# t-maze-shield.net
KiCad netlist of a schematic drawn in EAGLE
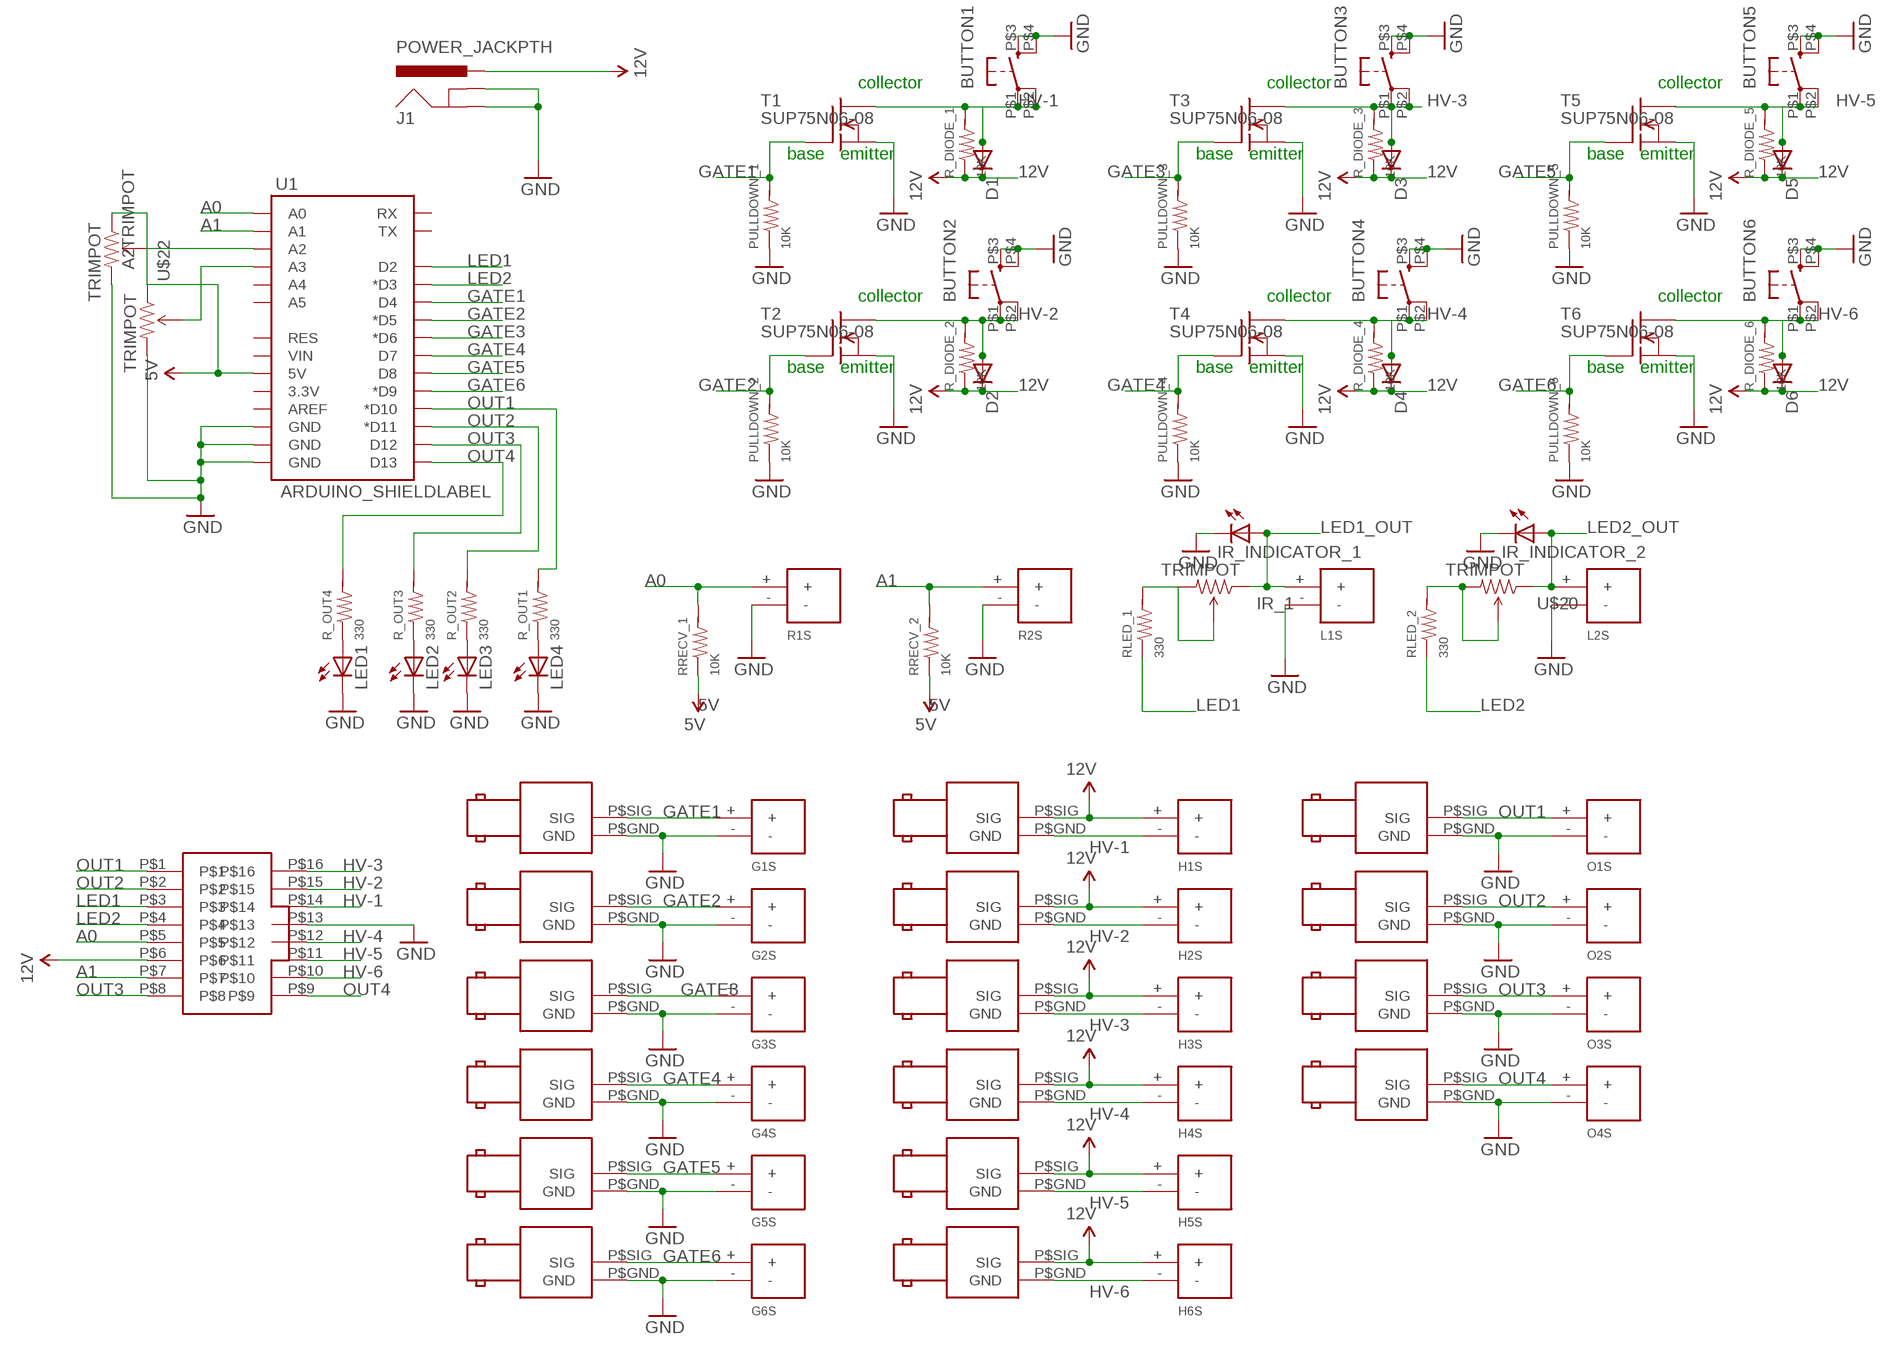
[diagram p0: schematic, sheet 1]

(export (version "E")
  (design (tool "Eeschema 10.0.6"))
  (components
    (comp (ref "A2TRIMPOT")
      (value "TRIMPOT")
      (footprint "eagle-import:3362U-2")
      (libsource (lib "eagle-import") (part "TRIMPOT"))
    )
    (comp (ref "BUTTON1")
      (value "TAC_SWITCHKSA_SEALED")
      (footprint "eagle-import:KSA_SEALED_TAC_SWITCH")
      (libsource (lib "eagle-import") (part "TAC_SWITCHKSA_SEALED"))
    )
    (comp (ref "BUTTON2")
      (value "TAC_SWITCHKSA_SEALED")
      (footprint "eagle-import:KSA_SEALED_TAC_SWITCH")
      (libsource (lib "eagle-import") (part "TAC_SWITCHKSA_SEALED"))
    )
    (comp (ref "BUTTON3")
      (value "TAC_SWITCHKSA_SEALED")
      (footprint "eagle-import:KSA_SEALED_TAC_SWITCH")
      (libsource (lib "eagle-import") (part "TAC_SWITCHKSA_SEALED"))
    )
    (comp (ref "BUTTON4")
      (value "TAC_SWITCHKSA_SEALED")
      (footprint "eagle-import:KSA_SEALED_TAC_SWITCH")
      (libsource (lib "eagle-import") (part "TAC_SWITCHKSA_SEALED"))
    )
    (comp (ref "BUTTON5")
      (value "TAC_SWITCHKSA_SEALED")
      (footprint "eagle-import:KSA_SEALED_TAC_SWITCH")
      (libsource (lib "eagle-import") (part "TAC_SWITCHKSA_SEALED"))
    )
    (comp (ref "BUTTON6")
      (value "TAC_SWITCHKSA_SEALED")
      (footprint "eagle-import:KSA_SEALED_TAC_SWITCH")
      (libsource (lib "eagle-import") (part "TAC_SWITCHKSA_SEALED"))
    )
    (comp (ref "D1")
      (value "DIODE1N4148")
      (footprint "eagle-import:DIODE-1N4148")
      (libsource (lib "eagle-import") (part "DIODE1N4148"))
    )
    (comp (ref "D2")
      (value "DIODE1N4148")
      (footprint "eagle-import:DIODE-1N4148")
      (libsource (lib "eagle-import") (part "DIODE1N4148"))
    )
    (comp (ref "D3")
      (value "DIODE1N4148")
      (footprint "eagle-import:DIODE-1N4148")
      (libsource (lib "eagle-import") (part "DIODE1N4148"))
    )
    (comp (ref "D4")
      (value "DIODE1N4148")
      (footprint "eagle-import:DIODE-1N4148")
      (libsource (lib "eagle-import") (part "DIODE1N4148"))
    )
    (comp (ref "D5")
      (value "DIODE1N4148")
      (footprint "eagle-import:DIODE-1N4148")
      (libsource (lib "eagle-import") (part "DIODE1N4148"))
    )
    (comp (ref "D6")
      (value "DIODE1N4148")
      (footprint "eagle-import:DIODE-1N4148")
      (libsource (lib "eagle-import") (part "DIODE1N4148"))
    )
    (comp (ref "G1S")
      (value "SCREW_TERM_2")
      (footprint "eagle-import:SCREW_TERM")
      (libsource (lib "eagle-import") (part "SCREW_TERM_2"))
    )
    (comp (ref "G2S")
      (value "SCREW_TERM_2")
      (footprint "eagle-import:SCREW_TERM")
      (libsource (lib "eagle-import") (part "SCREW_TERM_2"))
    )
    (comp (ref "G3S")
      (value "SCREW_TERM_2")
      (footprint "eagle-import:SCREW_TERM")
      (libsource (lib "eagle-import") (part "SCREW_TERM_2"))
    )
    (comp (ref "G4S")
      (value "SCREW_TERM_2")
      (footprint "eagle-import:SCREW_TERM")
      (libsource (lib "eagle-import") (part "SCREW_TERM_2"))
    )
    (comp (ref "G5S")
      (value "SCREW_TERM_2")
      (footprint "eagle-import:SCREW_TERM")
      (libsource (lib "eagle-import") (part "SCREW_TERM_2"))
    )
    (comp (ref "G6S")
      (value "SCREW_TERM_2")
      (footprint "eagle-import:SCREW_TERM")
      (libsource (lib "eagle-import") (part "SCREW_TERM_2"))
    )
    (comp (ref "GATE1")
      (value "BNC_RIGHT_ANGLE")
      (footprint "eagle-import:BNC_RIGHT_ANGLE")
      (libsource (lib "eagle-import") (part "BNC_RIGHT_ANGLE"))
    )
    (comp (ref "GATE2")
      (value "BNC_RIGHT_ANGLE")
      (footprint "eagle-import:BNC_RIGHT_ANGLE")
      (libsource (lib "eagle-import") (part "BNC_RIGHT_ANGLE"))
    )
    (comp (ref "GATE3")
      (value "BNC_RIGHT_ANGLE")
      (footprint "eagle-import:BNC_RIGHT_ANGLE")
      (libsource (lib "eagle-import") (part "BNC_RIGHT_ANGLE"))
    )
    (comp (ref "GATE4")
      (value "BNC_RIGHT_ANGLE")
      (footprint "eagle-import:BNC_RIGHT_ANGLE")
      (libsource (lib "eagle-import") (part "BNC_RIGHT_ANGLE"))
    )
    (comp (ref "GATE5")
      (value "BNC_RIGHT_ANGLE")
      (footprint "eagle-import:BNC_RIGHT_ANGLE")
      (libsource (lib "eagle-import") (part "BNC_RIGHT_ANGLE"))
    )
    (comp (ref "GATE6")
      (value "BNC_RIGHT_ANGLE")
      (footprint "eagle-import:BNC_RIGHT_ANGLE")
      (libsource (lib "eagle-import") (part "BNC_RIGHT_ANGLE"))
    )
    (comp (ref "H1S")
      (value "SCREW_TERM_2")
      (footprint "eagle-import:SCREW_TERM")
      (libsource (lib "eagle-import") (part "SCREW_TERM_2"))
    )
    (comp (ref "H2S")
      (value "SCREW_TERM_2")
      (footprint "eagle-import:SCREW_TERM")
      (libsource (lib "eagle-import") (part "SCREW_TERM_2"))
    )
    (comp (ref "H3S")
      (value "SCREW_TERM_2")
      (footprint "eagle-import:SCREW_TERM")
      (libsource (lib "eagle-import") (part "SCREW_TERM_2"))
    )
    (comp (ref "H4S")
      (value "SCREW_TERM_2")
      (footprint "eagle-import:SCREW_TERM")
      (libsource (lib "eagle-import") (part "SCREW_TERM_2"))
    )
    (comp (ref "H5S")
      (value "SCREW_TERM_2")
      (footprint "eagle-import:SCREW_TERM")
      (libsource (lib "eagle-import") (part "SCREW_TERM_2"))
    )
    (comp (ref "H6S")
      (value "SCREW_TERM_2")
      (footprint "eagle-import:SCREW_TERM")
      (libsource (lib "eagle-import") (part "SCREW_TERM_2"))
    )
    (comp (ref "I/O1")
      (value "BNC_RIGHT_ANGLE")
      (footprint "eagle-import:BNC_RIGHT_ANGLE")
      (libsource (lib "eagle-import") (part "BNC_RIGHT_ANGLE"))
    )
    (comp (ref "I/O2")
      (value "BNC_RIGHT_ANGLE")
      (footprint "eagle-import:BNC_RIGHT_ANGLE")
      (libsource (lib "eagle-import") (part "BNC_RIGHT_ANGLE"))
    )
    (comp (ref "I/O3")
      (value "BNC_RIGHT_ANGLE")
      (footprint "eagle-import:BNC_RIGHT_ANGLE")
      (libsource (lib "eagle-import") (part "BNC_RIGHT_ANGLE"))
    )
    (comp (ref "I/O4")
      (value "BNC_RIGHT_ANGLE")
      (footprint "eagle-import:BNC_RIGHT_ANGLE")
      (libsource (lib "eagle-import") (part "BNC_RIGHT_ANGLE"))
    )
    (comp (ref "IDC-16")
      (value "IDC_16PIN")
      (footprint "eagle-import:IDC_16PIN")
      (libsource (lib "eagle-import") (part "IDC_16PIN"))
    )
    (comp (ref "IR_1")
      (value "TRIMPOT")
      (footprint "eagle-import:3362U-2")
      (libsource (lib "eagle-import") (part "TRIMPOT"))
    )
    (comp (ref "IR_INDICATOR_1")
      (value "LED5MM")
      (footprint "eagle-import:LED5MM")
      (libsource (lib "eagle-import") (part "LED5MM"))
    )
    (comp (ref "IR_INDICATOR_2")
      (value "LED5MM")
      (footprint "eagle-import:LED5MM")
      (libsource (lib "eagle-import") (part "LED5MM"))
    )
    (comp (ref "J1")
      (value "POWER_JACKPTH")
      (footprint "eagle-import:POWER_JACK_PTH")
      (libsource (lib "eagle-import") (part "POWER_JACKPTH"))
    )
    (comp (ref "L1S")
      (value "SCREW_TERM_2")
      (footprint "eagle-import:SCREW_TERM")
      (libsource (lib "eagle-import") (part "SCREW_TERM_2"))
    )
    (comp (ref "L2S")
      (value "SCREW_TERM_2")
      (footprint "eagle-import:SCREW_TERM")
      (libsource (lib "eagle-import") (part "SCREW_TERM_2"))
    )
    (comp (ref "LED1")
      (value "LED5MM")
      (footprint "eagle-import:LED5MM")
      (libsource (lib "eagle-import") (part "LED5MM"))
    )
    (comp (ref "LED2")
      (value "LED5MM")
      (footprint "eagle-import:LED5MM")
      (libsource (lib "eagle-import") (part "LED5MM"))
    )
    (comp (ref "LED3")
      (value "LED5MM")
      (footprint "eagle-import:LED5MM")
      (libsource (lib "eagle-import") (part "LED5MM"))
    )
    (comp (ref "LED4")
      (value "LED5MM")
      (footprint "eagle-import:LED5MM")
      (libsource (lib "eagle-import") (part "LED5MM"))
    )
    (comp (ref "O1S")
      (value "SCREW_TERM_2")
      (footprint "eagle-import:SCREW_TERM")
      (libsource (lib "eagle-import") (part "SCREW_TERM_2"))
    )
    (comp (ref "O2S")
      (value "SCREW_TERM_2")
      (footprint "eagle-import:SCREW_TERM")
      (libsource (lib "eagle-import") (part "SCREW_TERM_2"))
    )
    (comp (ref "O3S")
      (value "SCREW_TERM_2")
      (footprint "eagle-import:SCREW_TERM")
      (libsource (lib "eagle-import") (part "SCREW_TERM_2"))
    )
    (comp (ref "O4S")
      (value "SCREW_TERM_2")
      (footprint "eagle-import:SCREW_TERM")
      (libsource (lib "eagle-import") (part "SCREW_TERM_2"))
    )
    (comp (ref "OUT1")
      (value "BNC_RIGHT_ANGLE")
      (footprint "eagle-import:BNC_RIGHT_ANGLE")
      (libsource (lib "eagle-import") (part "BNC_RIGHT_ANGLE"))
    )
    (comp (ref "OUT2")
      (value "BNC_RIGHT_ANGLE")
      (footprint "eagle-import:BNC_RIGHT_ANGLE")
      (libsource (lib "eagle-import") (part "BNC_RIGHT_ANGLE"))
    )
    (comp (ref "OUT3")
      (value "BNC_RIGHT_ANGLE")
      (footprint "eagle-import:BNC_RIGHT_ANGLE")
      (libsource (lib "eagle-import") (part "BNC_RIGHT_ANGLE"))
    )
    (comp (ref "OUT4")
      (value "BNC_RIGHT_ANGLE")
      (footprint "eagle-import:BNC_RIGHT_ANGLE")
      (libsource (lib "eagle-import") (part "BNC_RIGHT_ANGLE"))
    )
    (comp (ref "OUT5")
      (value "BNC_RIGHT_ANGLE")
      (footprint "eagle-import:BNC_RIGHT_ANGLE")
      (libsource (lib "eagle-import") (part "BNC_RIGHT_ANGLE"))
    )
    (comp (ref "OUT6")
      (value "BNC_RIGHT_ANGLE")
      (footprint "eagle-import:BNC_RIGHT_ANGLE")
      (libsource (lib "eagle-import") (part "BNC_RIGHT_ANGLE"))
    )
    (comp (ref "PULLDOWN_1")
      (value "10K")
      (footprint "eagle-import:RESISTOR_PTH")
      (libsource (lib "eagle-import") (part "RESISTOR_PTH"))
    )
    (comp (ref "PULLDOWN_2")
      (value "10K")
      (footprint "eagle-import:RESISTOR_PTH")
      (libsource (lib "eagle-import") (part "RESISTOR_PTH"))
    )
    (comp (ref "PULLDOWN_3")
      (value "10K")
      (footprint "eagle-import:RESISTOR_PTH")
      (libsource (lib "eagle-import") (part "RESISTOR_PTH"))
    )
    (comp (ref "PULLDOWN_4")
      (value "10K")
      (footprint "eagle-import:RESISTOR_PTH")
      (libsource (lib "eagle-import") (part "RESISTOR_PTH"))
    )
    (comp (ref "PULLDOWN_5")
      (value "10K")
      (footprint "eagle-import:RESISTOR_PTH")
      (libsource (lib "eagle-import") (part "RESISTOR_PTH"))
    )
    (comp (ref "PULLDOWN_6")
      (value "10K")
      (footprint "eagle-import:RESISTOR_PTH")
      (libsource (lib "eagle-import") (part "RESISTOR_PTH"))
    )
    (comp (ref "R1S")
      (value "SCREW_TERM_2")
      (footprint "eagle-import:SCREW_TERM")
      (libsource (lib "eagle-import") (part "SCREW_TERM_2"))
    )
    (comp (ref "R2S")
      (value "SCREW_TERM_2")
      (footprint "eagle-import:SCREW_TERM")
      (libsource (lib "eagle-import") (part "SCREW_TERM_2"))
    )
    (comp (ref "RLED_1")
      (value "330")
      (footprint "eagle-import:RESISTOR_PTH")
      (libsource (lib "eagle-import") (part "RESISTOR_PTH"))
    )
    (comp (ref "RLED_2")
      (value "330")
      (footprint "eagle-import:RESISTOR_PTH")
      (libsource (lib "eagle-import") (part "RESISTOR_PTH"))
    )
    (comp (ref "RRECV_1")
      (value "10K")
      (footprint "eagle-import:RESISTOR_PTH")
      (libsource (lib "eagle-import") (part "RESISTOR_PTH"))
    )
    (comp (ref "RRECV_2")
      (value "10K")
      (footprint "eagle-import:RESISTOR_PTH")
      (libsource (lib "eagle-import") (part "RESISTOR_PTH"))
    )
    (comp (ref "R_DIODE_1")
      (value "10K")
      (footprint "eagle-import:RESISTOR_PTH")
      (libsource (lib "eagle-import") (part "RESISTOR_PTH"))
    )
    (comp (ref "R_DIODE_2")
      (value "10K")
      (footprint "eagle-import:RESISTOR_PTH")
      (libsource (lib "eagle-import") (part "RESISTOR_PTH"))
    )
    (comp (ref "R_DIODE_3")
      (value "10K")
      (footprint "eagle-import:RESISTOR_PTH")
      (libsource (lib "eagle-import") (part "RESISTOR_PTH"))
    )
    (comp (ref "R_DIODE_4")
      (value "10K")
      (footprint "eagle-import:RESISTOR_PTH")
      (libsource (lib "eagle-import") (part "RESISTOR_PTH"))
    )
    (comp (ref "R_DIODE_5")
      (value "10K")
      (footprint "eagle-import:RESISTOR_PTH")
      (libsource (lib "eagle-import") (part "RESISTOR_PTH"))
    )
    (comp (ref "R_DIODE_6")
      (value "10K")
      (footprint "eagle-import:RESISTOR_PTH")
      (libsource (lib "eagle-import") (part "RESISTOR_PTH"))
    )
    (comp (ref "R_OUT1")
      (value "330")
      (footprint "eagle-import:RESISTOR_PTH")
      (libsource (lib "eagle-import") (part "RESISTOR_PTH"))
    )
    (comp (ref "R_OUT2")
      (value "330")
      (footprint "eagle-import:RESISTOR_PTH")
      (libsource (lib "eagle-import") (part "RESISTOR_PTH"))
    )
    (comp (ref "R_OUT3")
      (value "330")
      (footprint "eagle-import:RESISTOR_PTH")
      (libsource (lib "eagle-import") (part "RESISTOR_PTH"))
    )
    (comp (ref "R_OUT4")
      (value "330")
      (footprint "eagle-import:RESISTOR_PTH")
      (libsource (lib "eagle-import") (part "RESISTOR_PTH"))
    )
    (comp (ref "T1")
      (value "SUP75N06-08")
      (footprint "eagle-import:TO220")
      (libsource (lib "eagle-import") (part "SUP75N06-08"))
    )
    (comp (ref "T2")
      (value "SUP75N06-08")
      (footprint "eagle-import:TO220")
      (libsource (lib "eagle-import") (part "SUP75N06-08"))
    )
    (comp (ref "T3")
      (value "SUP75N06-08")
      (footprint "eagle-import:TO220")
      (libsource (lib "eagle-import") (part "SUP75N06-08"))
    )
    (comp (ref "T4")
      (value "SUP75N06-08")
      (footprint "eagle-import:TO220")
      (libsource (lib "eagle-import") (part "SUP75N06-08"))
    )
    (comp (ref "T5")
      (value "SUP75N06-08")
      (footprint "eagle-import:TO220")
      (libsource (lib "eagle-import") (part "SUP75N06-08"))
    )
    (comp (ref "T6")
      (value "SUP75N06-08")
      (footprint "eagle-import:TO220")
      (libsource (lib "eagle-import") (part "SUP75N06-08"))
    )
    (comp (ref "U$20")
      (value "TRIMPOT")
      (footprint "eagle-import:3362U-2")
      (libsource (lib "eagle-import") (part "TRIMPOT"))
    )
    (comp (ref "U$22")
      (value "TRIMPOT")
      (footprint "eagle-import:3362U-2")
      (libsource (lib "eagle-import") (part "TRIMPOT"))
    )
    (comp (ref "U1")
      (value "ARDUINO_SHIELDLABEL")
      (footprint "eagle-import:DUEMILANOVE_SHIELD")
      (libsource (lib "eagle-import") (part "ARDUINO_SHIELDLABEL"))
    )
  )
  (nets
    (net (code "1") (name "/A0") (class "Default")
      (node (ref "IDC-16") (pin "P$5") (pinfunction "P$5_P$5") (pintype "bidirectional"))
      (node (ref "R1S") (pin "+") (pinfunction "+_+") (pintype "bidirectional"))
      (node (ref "RRECV_1") (pin "P$2") (pinfunction "P$2_P$2") (pintype "bidirectional"))
      (node (ref "U1") (pin "A0") (pinfunction "A0_A0") (pintype "bidirectional"))
    )
    (net (code "2") (name "/A1") (class "Default")
      (node (ref "IDC-16") (pin "P$7") (pinfunction "P$7_P$7") (pintype "bidirectional"))
      (node (ref "R2S") (pin "+") (pinfunction "+_+") (pintype "bidirectional"))
      (node (ref "RRECV_2") (pin "P$2") (pinfunction "P$2_P$2") (pintype "bidirectional"))
      (node (ref "U1") (pin "A1") (pinfunction "A1_A1") (pintype "bidirectional"))
    )
    (net (code "3") (name "/GATE1") (class "Default")
      (node (ref "G1S") (pin "+") (pinfunction "+_+") (pintype "bidirectional"))
      (node (ref "GATE1") (pin "P$SIG") (pinfunction "SIG_P$SIG") (pintype "bidirectional"))
      (node (ref "PULLDOWN_1") (pin "P$2") (pinfunction "P$2_P$2") (pintype "bidirectional"))
      (node (ref "T1") (pin "1") (pinfunction "G_1") (pintype "passive"))
      (node (ref "U1") (pin "D4") (pinfunction "D4_D4") (pintype "bidirectional"))
    )
    (net (code "4") (name "/GATE2") (class "Default")
      (node (ref "G2S") (pin "+") (pinfunction "+_+") (pintype "bidirectional"))
      (node (ref "GATE2") (pin "P$SIG") (pinfunction "SIG_P$SIG") (pintype "bidirectional"))
      (node (ref "PULLDOWN_2") (pin "P$2") (pinfunction "P$2_P$2") (pintype "bidirectional"))
      (node (ref "T2") (pin "1") (pinfunction "G_1") (pintype "passive"))
      (node (ref "U1") (pin "D5") (pinfunction "*D5_D5") (pintype "bidirectional"))
    )
    (net (code "5") (name "/GATE3") (class "Default")
      (node (ref "G3S") (pin "+") (pinfunction "+_+") (pintype "bidirectional"))
      (node (ref "GATE3") (pin "P$SIG") (pinfunction "SIG_P$SIG") (pintype "bidirectional"))
      (node (ref "PULLDOWN_3") (pin "P$2") (pinfunction "P$2_P$2") (pintype "bidirectional"))
      (node (ref "T3") (pin "1") (pinfunction "G_1") (pintype "passive"))
      (node (ref "U1") (pin "D6") (pinfunction "*D6_D6") (pintype "bidirectional"))
    )
    (net (code "6") (name "/GATE4") (class "Default")
      (node (ref "G4S") (pin "+") (pinfunction "+_+") (pintype "bidirectional"))
      (node (ref "GATE4") (pin "P$SIG") (pinfunction "SIG_P$SIG") (pintype "bidirectional"))
      (node (ref "PULLDOWN_4") (pin "P$2") (pinfunction "P$2_P$2") (pintype "bidirectional"))
      (node (ref "T4") (pin "1") (pinfunction "G_1") (pintype "passive"))
      (node (ref "U1") (pin "D7") (pinfunction "D7_D7") (pintype "bidirectional"))
    )
    (net (code "7") (name "/GATE5") (class "Default")
      (node (ref "G5S") (pin "+") (pinfunction "+_+") (pintype "bidirectional"))
      (node (ref "GATE5") (pin "P$SIG") (pinfunction "SIG_P$SIG") (pintype "bidirectional"))
      (node (ref "PULLDOWN_5") (pin "P$2") (pinfunction "P$2_P$2") (pintype "bidirectional"))
      (node (ref "T5") (pin "1") (pinfunction "G_1") (pintype "passive"))
      (node (ref "U1") (pin "D8") (pinfunction "D8_D8") (pintype "bidirectional"))
    )
    (net (code "8") (name "/GATE6") (class "Default")
      (node (ref "G6S") (pin "+") (pinfunction "+_+") (pintype "bidirectional"))
      (node (ref "GATE6") (pin "P$SIG") (pinfunction "SIG_P$SIG") (pintype "bidirectional"))
      (node (ref "PULLDOWN_6") (pin "P$2") (pinfunction "P$2_P$2") (pintype "bidirectional"))
      (node (ref "T6") (pin "1") (pinfunction "G_1") (pintype "passive"))
      (node (ref "U1") (pin "D9") (pinfunction "*D9_D9") (pintype "bidirectional"))
    )
    (net (code "9") (name "/HV-1") (class "Default")
      (node (ref "BUTTON1") (pin "P$1") (pinfunction "1_P$1") (pintype "passive"))
      (node (ref "BUTTON1") (pin "P$2") (pinfunction "2_P$2") (pintype "passive"))
      (node (ref "D1") (pin "A") (pinfunction "A_A") (pintype "passive"))
      (node (ref "H1S") (pin "-") (pinfunction "-_-") (pintype "bidirectional"))
      (node (ref "IDC-16") (pin "P$14") (pinfunction "P$14_P$14") (pintype "bidirectional"))
      (node (ref "OUT1") (pin "P$GND") (pinfunction "GND_P$GND") (pintype "bidirectional"))
      (node (ref "R_DIODE_1") (pin "P$2") (pinfunction "P$2_P$2") (pintype "bidirectional"))
      (node (ref "T1") (pin "2") (pinfunction "D_2") (pintype "passive"))
    )
    (net (code "10") (name "/HV-2") (class "Default")
      (node (ref "BUTTON2") (pin "P$1") (pinfunction "1_P$1") (pintype "passive"))
      (node (ref "BUTTON2") (pin "P$2") (pinfunction "2_P$2") (pintype "passive"))
      (node (ref "D2") (pin "A") (pinfunction "A_A") (pintype "passive"))
      (node (ref "H2S") (pin "-") (pinfunction "-_-") (pintype "bidirectional"))
      (node (ref "IDC-16") (pin "P$15") (pinfunction "P$15_P$15") (pintype "bidirectional"))
      (node (ref "OUT2") (pin "P$GND") (pinfunction "GND_P$GND") (pintype "bidirectional"))
      (node (ref "R_DIODE_2") (pin "P$2") (pinfunction "P$2_P$2") (pintype "bidirectional"))
      (node (ref "T2") (pin "2") (pinfunction "D_2") (pintype "passive"))
    )
    (net (code "11") (name "/HV-3") (class "Default")
      (node (ref "BUTTON3") (pin "P$1") (pinfunction "1_P$1") (pintype "passive"))
      (node (ref "BUTTON3") (pin "P$2") (pinfunction "2_P$2") (pintype "passive"))
      (node (ref "D3") (pin "A") (pinfunction "A_A") (pintype "passive"))
      (node (ref "H3S") (pin "-") (pinfunction "-_-") (pintype "bidirectional"))
      (node (ref "IDC-16") (pin "P$16") (pinfunction "P$16_P$16") (pintype "bidirectional"))
      (node (ref "OUT3") (pin "P$GND") (pinfunction "GND_P$GND") (pintype "bidirectional"))
      (node (ref "R_DIODE_3") (pin "P$2") (pinfunction "P$2_P$2") (pintype "bidirectional"))
      (node (ref "T3") (pin "2") (pinfunction "D_2") (pintype "passive"))
    )
    (net (code "12") (name "/HV-4") (class "Default")
      (node (ref "BUTTON4") (pin "P$1") (pinfunction "1_P$1") (pintype "passive"))
      (node (ref "BUTTON4") (pin "P$2") (pinfunction "2_P$2") (pintype "passive"))
      (node (ref "D4") (pin "A") (pinfunction "A_A") (pintype "passive"))
      (node (ref "H4S") (pin "-") (pinfunction "-_-") (pintype "bidirectional"))
      (node (ref "IDC-16") (pin "P$12") (pinfunction "P$12_P$12") (pintype "bidirectional"))
      (node (ref "OUT4") (pin "P$GND") (pinfunction "GND_P$GND") (pintype "bidirectional"))
      (node (ref "R_DIODE_4") (pin "P$2") (pinfunction "P$2_P$2") (pintype "bidirectional"))
      (node (ref "T4") (pin "2") (pinfunction "D_2") (pintype "passive"))
    )
    (net (code "13") (name "/HV-5") (class "Default")
      (node (ref "BUTTON5") (pin "P$1") (pinfunction "1_P$1") (pintype "passive"))
      (node (ref "BUTTON5") (pin "P$2") (pinfunction "2_P$2") (pintype "passive"))
      (node (ref "D5") (pin "A") (pinfunction "A_A") (pintype "passive"))
      (node (ref "H5S") (pin "-") (pinfunction "-_-") (pintype "bidirectional"))
      (node (ref "IDC-16") (pin "P$11") (pinfunction "P$11_P$11") (pintype "bidirectional"))
      (node (ref "OUT5") (pin "P$GND") (pinfunction "GND_P$GND") (pintype "bidirectional"))
      (node (ref "R_DIODE_5") (pin "P$2") (pinfunction "P$2_P$2") (pintype "bidirectional"))
      (node (ref "T5") (pin "2") (pinfunction "D_2") (pintype "passive"))
    )
    (net (code "14") (name "/HV-6") (class "Default")
      (node (ref "BUTTON6") (pin "P$1") (pinfunction "1_P$1") (pintype "passive"))
      (node (ref "BUTTON6") (pin "P$2") (pinfunction "2_P$2") (pintype "passive"))
      (node (ref "D6") (pin "A") (pinfunction "A_A") (pintype "passive"))
      (node (ref "H6S") (pin "-") (pinfunction "-_-") (pintype "bidirectional"))
      (node (ref "IDC-16") (pin "P$10") (pinfunction "P$10_P$10") (pintype "bidirectional"))
      (node (ref "OUT6") (pin "P$GND") (pinfunction "GND_P$GND") (pintype "bidirectional"))
      (node (ref "R_DIODE_6") (pin "P$2") (pinfunction "P$2_P$2") (pintype "bidirectional"))
      (node (ref "T6") (pin "2") (pinfunction "D_2") (pintype "passive"))
    )
    (net (code "15") (name "/LED1") (class "Default")
      (node (ref "IDC-16") (pin "P$3") (pinfunction "P$3_P$3") (pintype "bidirectional"))
      (node (ref "RLED_1") (pin "P$1") (pinfunction "P$1_P$1") (pintype "bidirectional"))
      (node (ref "U1") (pin "D2") (pinfunction "D2_D2") (pintype "bidirectional"))
    )
    (net (code "16") (name "/LED1_OUT") (class "Default")
      (node (ref "IR_1") (pin "1") (pinfunction "CCW_1") (pintype "passive"))
      (node (ref "IR_INDICATOR_1") (pin "A") (pinfunction "A_A") (pintype "passive"))
      (node (ref "L1S") (pin "+") (pinfunction "+_+") (pintype "bidirectional"))
    )
    (net (code "17") (name "/LED2") (class "Default")
      (node (ref "IDC-16") (pin "P$4") (pinfunction "P$4_P$4") (pintype "bidirectional"))
      (node (ref "RLED_2") (pin "P$1") (pinfunction "P$1_P$1") (pintype "bidirectional"))
      (node (ref "U1") (pin "D3") (pinfunction "*D3_D3") (pintype "bidirectional"))
    )
    (net (code "18") (name "/LED2_OUT") (class "Default")
      (node (ref "IR_INDICATOR_2") (pin "A") (pinfunction "A_A") (pintype "passive"))
      (node (ref "L2S") (pin "+") (pinfunction "+_+") (pintype "bidirectional"))
      (node (ref "U$20") (pin "1") (pinfunction "CCW_1") (pintype "passive"))
    )
    (net (code "19") (name "/OUT1") (class "Default")
      (node (ref "I/O1") (pin "P$SIG") (pinfunction "SIG_P$SIG") (pintype "bidirectional"))
      (node (ref "IDC-16") (pin "P$1") (pinfunction "P$1_P$1") (pintype "bidirectional"))
      (node (ref "O1S") (pin "+") (pinfunction "+_+") (pintype "bidirectional"))
      (node (ref "R_OUT1") (pin "P$2") (pinfunction "P$2_P$2") (pintype "bidirectional"))
      (node (ref "U1") (pin "D10") (pinfunction "*D10_D10") (pintype "bidirectional"))
    )
    (net (code "20") (name "/OUT2") (class "Default")
      (node (ref "I/O2") (pin "P$SIG") (pinfunction "SIG_P$SIG") (pintype "bidirectional"))
      (node (ref "IDC-16") (pin "P$2") (pinfunction "P$2_P$2") (pintype "bidirectional"))
      (node (ref "O2S") (pin "+") (pinfunction "+_+") (pintype "bidirectional"))
      (node (ref "R_OUT2") (pin "P$2") (pinfunction "P$2_P$2") (pintype "bidirectional"))
      (node (ref "U1") (pin "D11") (pinfunction "*D11_D11") (pintype "bidirectional"))
    )
    (net (code "21") (name "/OUT3") (class "Default")
      (node (ref "I/O3") (pin "P$SIG") (pinfunction "SIG_P$SIG") (pintype "bidirectional"))
      (node (ref "IDC-16") (pin "P$8") (pinfunction "P$8_P$8") (pintype "bidirectional"))
      (node (ref "O3S") (pin "+") (pinfunction "+_+") (pintype "bidirectional"))
      (node (ref "R_OUT3") (pin "P$2") (pinfunction "P$2_P$2") (pintype "bidirectional"))
      (node (ref "U1") (pin "D12") (pinfunction "D12_D12") (pintype "bidirectional"))
    )
    (net (code "22") (name "/OUT4") (class "Default")
      (node (ref "I/O4") (pin "P$SIG") (pinfunction "SIG_P$SIG") (pintype "bidirectional"))
      (node (ref "IDC-16") (pin "P$9") (pinfunction "P$9_P$9") (pintype "bidirectional"))
      (node (ref "O4S") (pin "+") (pinfunction "+_+") (pintype "bidirectional"))
      (node (ref "R_OUT4") (pin "P$2") (pinfunction "P$2_P$2") (pintype "bidirectional"))
      (node (ref "U1") (pin "D13") (pinfunction "D13_D13") (pintype "bidirectional"))
    )
    (net (code "23") (name "5V") (class "Default")
      (node (ref "A2TRIMPOT") (pin "1") (pinfunction "CCW_1") (pintype "passive"))
      (node (ref "RRECV_1") (pin "P$1") (pinfunction "P$1_P$1") (pintype "bidirectional"))
      (node (ref "RRECV_2") (pin "P$1") (pinfunction "P$1_P$1") (pintype "bidirectional"))
      (node (ref "U$22") (pin "1") (pinfunction "CCW_1") (pintype "passive"))
      (node (ref "U1") (pin "5V") (pinfunction "5V_5V") (pintype "bidirectional"))
    )
    (net (code "24") (name "12V") (class "Default")
      (node (ref "D1") (pin "C") (pinfunction "C_C") (pintype "passive"))
      (node (ref "D2") (pin "C") (pinfunction "C_C") (pintype "passive"))
      (node (ref "D3") (pin "C") (pinfunction "C_C") (pintype "passive"))
      (node (ref "D4") (pin "C") (pinfunction "C_C") (pintype "passive"))
      (node (ref "D5") (pin "C") (pinfunction "C_C") (pintype "passive"))
      (node (ref "D6") (pin "C") (pinfunction "C_C") (pintype "passive"))
      (node (ref "H1S") (pin "+") (pinfunction "+_+") (pintype "bidirectional"))
      (node (ref "H2S") (pin "+") (pinfunction "+_+") (pintype "bidirectional"))
      (node (ref "H3S") (pin "+") (pinfunction "+_+") (pintype "bidirectional"))
      (node (ref "H4S") (pin "+") (pinfunction "+_+") (pintype "bidirectional"))
      (node (ref "H5S") (pin "+") (pinfunction "+_+") (pintype "bidirectional"))
      (node (ref "H6S") (pin "+") (pinfunction "+_+") (pintype "bidirectional"))
      (node (ref "IDC-16") (pin "P$6") (pinfunction "P$6_P$6") (pintype "bidirectional"))
      (node (ref "J1") (pin "PWR") (pinfunction "PWR_PWR") (pintype "bidirectional"))
      (node (ref "OUT1") (pin "P$SIG") (pinfunction "SIG_P$SIG") (pintype "bidirectional"))
      (node (ref "OUT2") (pin "P$SIG") (pinfunction "SIG_P$SIG") (pintype "bidirectional"))
      (node (ref "OUT3") (pin "P$SIG") (pinfunction "SIG_P$SIG") (pintype "bidirectional"))
      (node (ref "OUT4") (pin "P$SIG") (pinfunction "SIG_P$SIG") (pintype "bidirectional"))
      (node (ref "OUT5") (pin "P$SIG") (pinfunction "SIG_P$SIG") (pintype "bidirectional"))
      (node (ref "OUT6") (pin "P$SIG") (pinfunction "SIG_P$SIG") (pintype "bidirectional"))
      (node (ref "R_DIODE_1") (pin "P$1") (pinfunction "P$1_P$1") (pintype "bidirectional"))
      (node (ref "R_DIODE_2") (pin "P$1") (pinfunction "P$1_P$1") (pintype "bidirectional"))
      (node (ref "R_DIODE_3") (pin "P$1") (pinfunction "P$1_P$1") (pintype "bidirectional"))
      (node (ref "R_DIODE_4") (pin "P$1") (pinfunction "P$1_P$1") (pintype "bidirectional"))
      (node (ref "R_DIODE_5") (pin "P$1") (pinfunction "P$1_P$1") (pintype "bidirectional"))
      (node (ref "R_DIODE_6") (pin "P$1") (pinfunction "P$1_P$1") (pintype "bidirectional"))
    )
    (net (code "25") (name "GND") (class "Default")
      (node (ref "A2TRIMPOT") (pin "3") (pinfunction "CW_3") (pintype "passive"))
      (node (ref "BUTTON1") (pin "P$3") (pinfunction "3_P$3") (pintype "passive"))
      (node (ref "BUTTON1") (pin "P$4") (pinfunction "4_P$4") (pintype "passive"))
      (node (ref "BUTTON2") (pin "P$3") (pinfunction "3_P$3") (pintype "passive"))
      (node (ref "BUTTON2") (pin "P$4") (pinfunction "4_P$4") (pintype "passive"))
      (node (ref "BUTTON3") (pin "P$3") (pinfunction "3_P$3") (pintype "passive"))
      (node (ref "BUTTON3") (pin "P$4") (pinfunction "4_P$4") (pintype "passive"))
      (node (ref "BUTTON4") (pin "P$3") (pinfunction "3_P$3") (pintype "passive"))
      (node (ref "BUTTON4") (pin "P$4") (pinfunction "4_P$4") (pintype "passive"))
      (node (ref "BUTTON5") (pin "P$3") (pinfunction "3_P$3") (pintype "passive"))
      (node (ref "BUTTON5") (pin "P$4") (pinfunction "4_P$4") (pintype "passive"))
      (node (ref "BUTTON6") (pin "P$3") (pinfunction "3_P$3") (pintype "passive"))
      (node (ref "BUTTON6") (pin "P$4") (pinfunction "4_P$4") (pintype "passive"))
      (node (ref "G1S") (pin "-") (pinfunction "-_-") (pintype "bidirectional"))
      (node (ref "G2S") (pin "-") (pinfunction "-_-") (pintype "bidirectional"))
      (node (ref "G3S") (pin "-") (pinfunction "-_-") (pintype "bidirectional"))
      (node (ref "G4S") (pin "-") (pinfunction "-_-") (pintype "bidirectional"))
      (node (ref "G5S") (pin "-") (pinfunction "-_-") (pintype "bidirectional"))
      (node (ref "G6S") (pin "-") (pinfunction "-_-") (pintype "bidirectional"))
      (node (ref "GATE1") (pin "P$GND") (pinfunction "GND_P$GND") (pintype "bidirectional"))
      (node (ref "GATE2") (pin "P$GND") (pinfunction "GND_P$GND") (pintype "bidirectional"))
      (node (ref "GATE3") (pin "P$GND") (pinfunction "GND_P$GND") (pintype "bidirectional"))
      (node (ref "GATE4") (pin "P$GND") (pinfunction "GND_P$GND") (pintype "bidirectional"))
      (node (ref "GATE5") (pin "P$GND") (pinfunction "GND_P$GND") (pintype "bidirectional"))
      (node (ref "GATE6") (pin "P$GND") (pinfunction "GND_P$GND") (pintype "bidirectional"))
      (node (ref "I/O1") (pin "P$GND") (pinfunction "GND_P$GND") (pintype "bidirectional"))
      (node (ref "I/O2") (pin "P$GND") (pinfunction "GND_P$GND") (pintype "bidirectional"))
      (node (ref "I/O3") (pin "P$GND") (pinfunction "GND_P$GND") (pintype "bidirectional"))
      (node (ref "I/O4") (pin "P$GND") (pinfunction "GND_P$GND") (pintype "bidirectional"))
      (node (ref "IDC-16") (pin "P$13") (pinfunction "P$13_P$13") (pintype "bidirectional"))
      (node (ref "IR_INDICATOR_1") (pin "K") (pinfunction "C_K") (pintype "passive"))
      (node (ref "IR_INDICATOR_2") (pin "K") (pinfunction "C_K") (pintype "passive"))
      (node (ref "J1") (pin "GND") (pinfunction "GND_GND") (pintype "bidirectional"))
      (node (ref "J1") (pin "GNDBREAK") (pinfunction "GNDBREAK_GNDBREAK") (pintype "bidirectional"))
      (node (ref "L1S") (pin "-") (pinfunction "-_-") (pintype "bidirectional"))
      (node (ref "L2S") (pin "-") (pinfunction "-_-") (pintype "bidirectional"))
      (node (ref "LED1") (pin "K") (pinfunction "C_K") (pintype "passive"))
      (node (ref "LED2") (pin "K") (pinfunction "C_K") (pintype "passive"))
      (node (ref "LED3") (pin "K") (pinfunction "C_K") (pintype "passive"))
      (node (ref "LED4") (pin "K") (pinfunction "C_K") (pintype "passive"))
      (node (ref "O1S") (pin "-") (pinfunction "-_-") (pintype "bidirectional"))
      (node (ref "O2S") (pin "-") (pinfunction "-_-") (pintype "bidirectional"))
      (node (ref "O3S") (pin "-") (pinfunction "-_-") (pintype "bidirectional"))
      (node (ref "O4S") (pin "-") (pinfunction "-_-") (pintype "bidirectional"))
      (node (ref "PULLDOWN_1") (pin "P$1") (pinfunction "P$1_P$1") (pintype "bidirectional"))
      (node (ref "PULLDOWN_2") (pin "P$1") (pinfunction "P$1_P$1") (pintype "bidirectional"))
      (node (ref "PULLDOWN_3") (pin "P$1") (pinfunction "P$1_P$1") (pintype "bidirectional"))
      (node (ref "PULLDOWN_4") (pin "P$1") (pinfunction "P$1_P$1") (pintype "bidirectional"))
      (node (ref "PULLDOWN_5") (pin "P$1") (pinfunction "P$1_P$1") (pintype "bidirectional"))
      (node (ref "PULLDOWN_6") (pin "P$1") (pinfunction "P$1_P$1") (pintype "bidirectional"))
      (node (ref "R1S") (pin "-") (pinfunction "-_-") (pintype "bidirectional"))
      (node (ref "R2S") (pin "-") (pinfunction "-_-") (pintype "bidirectional"))
      (node (ref "T1") (pin "3") (pinfunction "S_3") (pintype "passive"))
      (node (ref "T2") (pin "3") (pinfunction "S_3") (pintype "passive"))
      (node (ref "T3") (pin "3") (pinfunction "S_3") (pintype "passive"))
      (node (ref "T4") (pin "3") (pinfunction "S_3") (pintype "passive"))
      (node (ref "T5") (pin "3") (pinfunction "S_3") (pintype "passive"))
      (node (ref "T6") (pin "3") (pinfunction "S_3") (pintype "passive"))
      (node (ref "U$22") (pin "3") (pinfunction "CW_3") (pintype "passive"))
      (node (ref "U1") (pin "GND@0") (pinfunction "GND_GND@0") (pintype "bidirectional"))
      (node (ref "U1") (pin "GND@1") (pinfunction "GND_GND@1") (pintype "bidirectional"))
      (node (ref "U1") (pin "GND@2") (pinfunction "GND_GND@2") (pintype "bidirectional"))
    )
    (net (code "26") (name "Net-(A2TRIMPOT-WIPER)") (class "Default")
      (node (ref "A2TRIMPOT") (pin "2") (pinfunction "WIPER_2") (pintype "passive"))
      (node (ref "U1") (pin "A2") (pinfunction "A2_A2") (pintype "bidirectional"))
    )
    (net (code "27") (name "Net-(IR_1-CW)") (class "Default")
      (node (ref "IR_1") (pin "2") (pinfunction "WIPER_2") (pintype "passive"))
      (node (ref "IR_1") (pin "3") (pinfunction "CW_3") (pintype "passive"))
      (node (ref "RLED_1") (pin "P$2") (pinfunction "P$2_P$2") (pintype "bidirectional"))
    )
    (net (code "28") (name "Net-(LED1-PadA)") (class "Default")
      (node (ref "LED1") (pin "A") (pinfunction "A_A") (pintype "passive"))
      (node (ref "R_OUT4") (pin "P$1") (pinfunction "P$1_P$1") (pintype "bidirectional"))
    )
    (net (code "29") (name "Net-(LED2-PadA)") (class "Default")
      (node (ref "LED2") (pin "A") (pinfunction "A_A") (pintype "passive"))
      (node (ref "R_OUT3") (pin "P$1") (pinfunction "P$1_P$1") (pintype "bidirectional"))
    )
    (net (code "30") (name "Net-(LED3-PadA)") (class "Default")
      (node (ref "LED3") (pin "A") (pinfunction "A_A") (pintype "passive"))
      (node (ref "R_OUT2") (pin "P$1") (pinfunction "P$1_P$1") (pintype "bidirectional"))
    )
    (net (code "31") (name "Net-(LED4-PadA)") (class "Default")
      (node (ref "LED4") (pin "A") (pinfunction "A_A") (pintype "passive"))
      (node (ref "R_OUT1") (pin "P$1") (pinfunction "P$1_P$1") (pintype "bidirectional"))
    )
    (net (code "32") (name "Net-(U$20-CW)") (class "Default")
      (node (ref "RLED_2") (pin "P$2") (pinfunction "P$2_P$2") (pintype "bidirectional"))
      (node (ref "U$20") (pin "2") (pinfunction "WIPER_2") (pintype "passive"))
      (node (ref "U$20") (pin "3") (pinfunction "CW_3") (pintype "passive"))
    )
    (net (code "33") (name "Net-(U$22-WIPER)") (class "Default")
      (node (ref "U$22") (pin "2") (pinfunction "WIPER_2") (pintype "passive"))
      (node (ref "U1") (pin "A3") (pinfunction "A3_A3") (pintype "bidirectional"))
    )
    (net (code "34") (name "unconnected-(U1-Pad3.3V)") (class "Default")
      (node (ref "U1") (pin "3.3V") (pinfunction "3.3V_3.3V") (pintype "bidirectional"))
    )
    (net (code "35") (name "unconnected-(U1-PadA4)") (class "Default")
      (node (ref "U1") (pin "A4") (pinfunction "A4_A4") (pintype "bidirectional"))
    )
    (net (code "36") (name "unconnected-(U1-PadA5)") (class "Default")
      (node (ref "U1") (pin "A5") (pinfunction "A5_A5") (pintype "bidirectional"))
    )
    (net (code "37") (name "unconnected-(U1-PadAREF)") (class "Default")
      (node (ref "U1") (pin "AREF") (pinfunction "AREF_AREF") (pintype "bidirectional"))
    )
    (net (code "38") (name "unconnected-(U1-PadRES)") (class "Default")
      (node (ref "U1") (pin "RES") (pinfunction "RES_RES") (pintype "bidirectional"))
    )
    (net (code "39") (name "unconnected-(U1-PadRX)") (class "Default")
      (node (ref "U1") (pin "RX") (pinfunction "RX_RX") (pintype "bidirectional"))
    )
    (net (code "40") (name "unconnected-(U1-PadTX)") (class "Default")
      (node (ref "U1") (pin "TX") (pinfunction "TX_TX") (pintype "bidirectional"))
    )
    (net (code "41") (name "unconnected-(U1-PadVIN)") (class "Default")
      (node (ref "U1") (pin "VIN") (pinfunction "VIN_VIN") (pintype "bidirectional"))
    )
  )
)
